# murdock_mcu.net
KiCad netlist of a schematic drawn in EAGLE
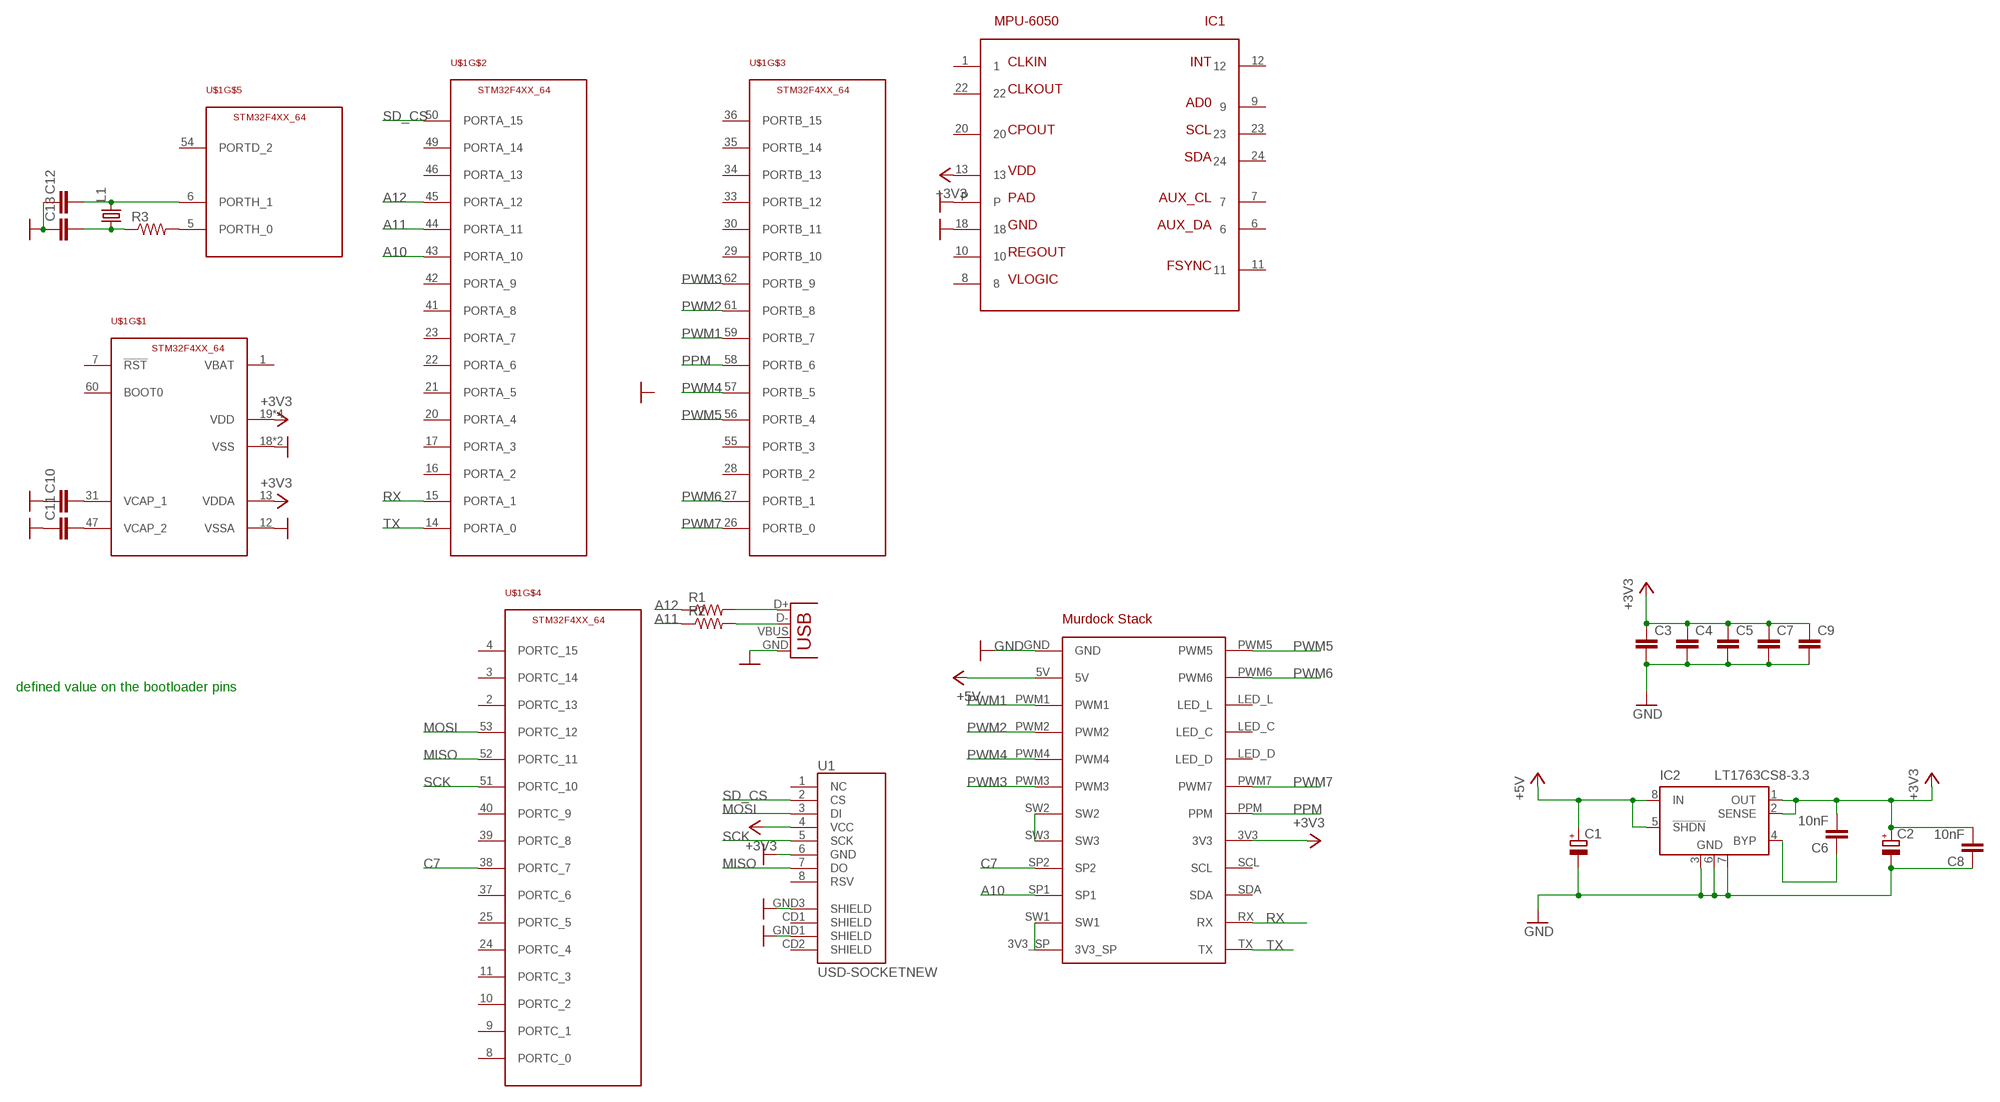
[diagram p0: schematic, sheet 1]

(export (version "E")
  (design (tool "Eeschema 10.0.6"))
  (components
    (comp (ref "C1")
      (value "CPOL-EUSMCD")
      (footprint "eagle-import:SMC_D")
      (libsource (lib "eagle-import") (part "CPOL-EUSMCD"))
    )
    (comp (ref "C2")
      (value "CPOL-EUSMCD")
      (footprint "eagle-import:SMC_D")
      (libsource (lib "eagle-import") (part "CPOL-EUSMCD"))
    )
    (comp (ref "C3")
      (value "CAP0402-CAP")
      (footprint "eagle-import:0402-CAP")
      (libsource (lib "eagle-import") (part "CAP0402-CAP"))
    )
    (comp (ref "C4")
      (value "CAP0402-CAP")
      (footprint "eagle-import:0402-CAP")
      (libsource (lib "eagle-import") (part "CAP0402-CAP"))
    )
    (comp (ref "C5")
      (value "CAP0402-CAP")
      (footprint "eagle-import:0402-CAP")
      (libsource (lib "eagle-import") (part "CAP0402-CAP"))
    )
    (comp (ref "C6")
      (value "10nF")
      (footprint "eagle-import:C0402")
      (libsource (lib "eagle-import") (part "C-EUC0402"))
    )
    (comp (ref "C7")
      (value "CAP0402-CAP")
      (footprint "eagle-import:0402-CAP")
      (libsource (lib "eagle-import") (part "CAP0402-CAP"))
    )
    (comp (ref "C8")
      (value "10nF")
      (footprint "eagle-import:C0402")
      (libsource (lib "eagle-import") (part "C-EUC0402"))
    )
    (comp (ref "C9")
      (value "CAP0402-CAP")
      (footprint "eagle-import:0402-CAP")
      (libsource (lib "eagle-import") (part "CAP0402-CAP"))
    )
    (comp (ref "C10")
      (value "CAP0805")
      (footprint "eagle-import:0805")
      (libsource (lib "eagle-import") (part "CAP0805"))
    )
    (comp (ref "C11")
      (value "CAP0805")
      (footprint "eagle-import:0805")
      (libsource (lib "eagle-import") (part "CAP0805"))
    )
    (comp (ref "C12")
      (value "CAP0402-CAP")
      (footprint "eagle-import:0402-CAP")
      (libsource (lib "eagle-import") (part "CAP0402-CAP"))
    )
    (comp (ref "C13")
      (value "CAP0402-CAP")
      (footprint "eagle-import:0402-CAP")
      (libsource (lib "eagle-import") (part "CAP0402-CAP"))
    )
    (comp (ref "IC1")
      (value "MPU-6050")
      (footprint "eagle-import:QFN24")
      (libsource (lib "eagle-import") (part "MPU-6050"))
    )
    (comp (ref "IC2")
      (value "LT1763CS8-3.3")
      (footprint "eagle-import:SOIC8")
      (libsource (lib "eagle-import") (part "LT1763CS8-3.3"))
    )
    (comp (ref "L1")
      (value "X22-OSCILLATOR")
      (footprint "eagle-import:X22")
      (libsource (lib "eagle-import") (part "X22-OSCILLATOR"))
    )
    (comp (ref "R1")
      (value "RESISTOR0402-RES")
      (footprint "eagle-import:0402-RES")
      (libsource (lib "eagle-import") (part "RESISTOR0402-RES"))
    )
    (comp (ref "R2")
      (value "RESISTOR0402-RES")
      (footprint "eagle-import:0402-RES")
      (libsource (lib "eagle-import") (part "RESISTOR0402-RES"))
    )
    (comp (ref "R3")
      (value "RESISTOR0402-RES")
      (footprint "eagle-import:0402-RES")
      (libsource (lib "eagle-import") (part "RESISTOR0402-RES"))
    )
    (comp (ref "U$1")
      (value "STM32F4XX_64")
      (footprint "eagle-import:TQFP64")
      (libsource (lib "eagle-import") (part "STM32F4XX_64"))
    )
    (comp (ref "U1")
      (value "USD-SOCKETNEW")
      (footprint "eagle-import:MICRO-SD-SOCKET-PP")
      (libsource (lib "eagle-import") (part "USD-SOCKETNEW"))
    )
    (comp (ref "X1")
      (value "USBSMD")
      (footprint "eagle-import:USB-MINIB")
      (libsource (lib "eagle-import") (part "USBSMD"))
    )
    (comp (ref "X2")
      (value "MURDOCK_STACK")
      (footprint "eagle-import:MURDOCK_STACK")
      (libsource (lib "eagle-import") (part "MURDOCK_STACK"))
    )
  )
  (nets
    (net (code "1") (name "+3V3") (class "Default")
      (node (ref "C2") (pin "+") (pinfunction "+_+") (pintype "passive"))
      (node (ref "C3") (pin "1") (pinfunction "1_1") (pintype "passive"))
      (node (ref "C4") (pin "1") (pinfunction "1_1") (pintype "passive"))
      (node (ref "C5") (pin "1") (pinfunction "1_1") (pintype "passive"))
      (node (ref "C6") (pin "2") (pinfunction "2_2") (pintype "passive"))
      (node (ref "C7") (pin "1") (pinfunction "1_1") (pintype "passive"))
      (node (ref "C8") (pin "2") (pinfunction "2_2") (pintype "passive"))
      (node (ref "C9") (pin "1") (pinfunction "1_1") (pintype "passive"))
      (node (ref "IC1") (pin "13") (pinfunction "13_13") (pintype "bidirectional"))
      (node (ref "IC2") (pin "1") (pinfunction "OUT_1") (pintype "passive"))
      (node (ref "IC2") (pin "2") (pinfunction "SENSE_2") (pintype "input"))
      (node (ref "U$1") (pin "13") (pinfunction "VDDA_13") (pintype "bidirectional"))
      (node (ref "U$1") (pin "19") (pinfunction "VDD_19") (pintype "bidirectional"))
      (node (ref "U$1") (pin "32") (pinfunction "VDD_32") (pintype "bidirectional"))
      (node (ref "U$1") (pin "48") (pinfunction "VDD_48") (pintype "bidirectional"))
      (node (ref "U$1") (pin "64") (pinfunction "VDD_64") (pintype "bidirectional"))
      (node (ref "U1") (pin "4") (pinfunction "VCC_4") (pintype "bidirectional"))
      (node (ref "X2") (pin "3V3") (pinfunction "3V3_3V3") (pintype "bidirectional"))
    )
    (net (code "2") (name "+5V") (class "Default")
      (node (ref "C1") (pin "+") (pinfunction "+_+") (pintype "passive"))
      (node (ref "IC2") (pin "5") (pinfunction "~{SHDN}_5") (pintype "input"))
      (node (ref "IC2") (pin "8") (pinfunction "IN_8") (pintype "input"))
      (node (ref "X2") (pin "5V") (pinfunction "5V_5V") (pintype "bidirectional"))
    )
    (net (code "3") (name "A10") (class "Default")
      (node (ref "U$1") (pin "43") (pinfunction "PORTA_10_43") (pintype "bidirectional"))
      (node (ref "X2") (pin "SP1") (pinfunction "SP1_SP1") (pintype "bidirectional"))
    )
    (net (code "4") (name "A11") (class "Default")
      (node (ref "R2") (pin "1") (pinfunction "1_1") (pintype "passive"))
      (node (ref "U$1") (pin "44") (pinfunction "PORTA_11_44") (pintype "bidirectional"))
    )
    (net (code "5") (name "A12") (class "Default")
      (node (ref "R1") (pin "1") (pinfunction "1_1") (pintype "passive"))
      (node (ref "U$1") (pin "45") (pinfunction "PORTA_12_45") (pintype "bidirectional"))
    )
    (net (code "6") (name "C7") (class "Default")
      (node (ref "U$1") (pin "38") (pinfunction "PORTC_7_38") (pintype "bidirectional"))
      (node (ref "X2") (pin "SP2") (pinfunction "SP2_SP2") (pintype "bidirectional"))
    )
    (net (code "7") (name "GND") (class "Default")
      (node (ref "C1") (pin "-") (pinfunction "-_-") (pintype "passive"))
      (node (ref "C10") (pin "1") (pinfunction "1_1") (pintype "passive"))
      (node (ref "C11") (pin "1") (pinfunction "1_1") (pintype "passive"))
      (node (ref "C12") (pin "1") (pinfunction "1_1") (pintype "passive"))
      (node (ref "C13") (pin "1") (pinfunction "1_1") (pintype "passive"))
      (node (ref "C2") (pin "-") (pinfunction "-_-") (pintype "passive"))
      (node (ref "C3") (pin "2") (pinfunction "2_2") (pintype "passive"))
      (node (ref "C4") (pin "2") (pinfunction "2_2") (pintype "passive"))
      (node (ref "C5") (pin "2") (pinfunction "2_2") (pintype "passive"))
      (node (ref "C7") (pin "2") (pinfunction "2_2") (pintype "passive"))
      (node (ref "C8") (pin "1") (pinfunction "1_1") (pintype "passive"))
      (node (ref "C9") (pin "2") (pinfunction "2_2") (pintype "passive"))
      (node (ref "IC1") (pin "18") (pinfunction "18_18") (pintype "bidirectional"))
      (node (ref "IC1") (pin "P") (pinfunction "P_P") (pintype "bidirectional"))
      (node (ref "IC2") (pin "3") (pinfunction "GND_3") (pintype "power_in"))
      (node (ref "IC2") (pin "6") (pinfunction "GND_6") (pintype "power_in"))
      (node (ref "IC2") (pin "7") (pinfunction "GND_7") (pintype "power_in"))
      (node (ref "U$1") (pin "12") (pinfunction "VSSA_12") (pintype "bidirectional"))
      (node (ref "U$1") (pin "18") (pinfunction "VSS_18") (pintype "bidirectional"))
      (node (ref "U$1") (pin "63") (pinfunction "VSS_63") (pintype "bidirectional"))
      (node (ref "U1") (pin "6") (pinfunction "GND_6") (pintype "bidirectional"))
      (node (ref "U1") (pin "GND1") (pinfunction "SHIELD_GND1") (pintype "bidirectional"))
      (node (ref "U1") (pin "GND3") (pinfunction "SHIELD_GND3") (pintype "bidirectional"))
      (node (ref "X1") (pin "GND") (pinfunction "GND_GND") (pintype "bidirectional"))
      (node (ref "X2") (pin "GND") (pinfunction "GND_GND") (pintype "bidirectional"))
    )
    (net (code "8") (name "MISO") (class "Default")
      (node (ref "U$1") (pin "52") (pinfunction "PORTC_11_52") (pintype "bidirectional"))
      (node (ref "U1") (pin "7") (pinfunction "DO_7") (pintype "bidirectional"))
    )
    (net (code "9") (name "MOSI") (class "Default")
      (node (ref "U$1") (pin "53") (pinfunction "PORTC_12_53") (pintype "bidirectional"))
      (node (ref "U1") (pin "3") (pinfunction "DI_3") (pintype "bidirectional"))
    )
    (net (code "10") (name "Net-(C13-Pad2)") (class "Default")
      (node (ref "C13") (pin "2") (pinfunction "2_2") (pintype "passive"))
      (node (ref "L1") (pin "1") (pinfunction "1_1") (pintype "passive"))
      (node (ref "R3") (pin "1") (pinfunction "1_1") (pintype "passive"))
    )
    (net (code "11") (name "Net-(IC2-BYP)") (class "Default")
      (node (ref "C6") (pin "1") (pinfunction "1_1") (pintype "passive"))
      (node (ref "IC2") (pin "4") (pinfunction "BYP_4") (pintype "input"))
    )
    (net (code "12") (name "Net-(L1-2)") (class "Default")
      (node (ref "C12") (pin "2") (pinfunction "2_2") (pintype "passive"))
      (node (ref "L1") (pin "3") (pinfunction "2_3") (pintype "passive"))
      (node (ref "U$1") (pin "6") (pinfunction "PORTH_1_6") (pintype "bidirectional"))
    )
    (net (code "13") (name "Net-(R1-Pad2)") (class "Default")
      (node (ref "R1") (pin "2") (pinfunction "2_2") (pintype "passive"))
      (node (ref "X1") (pin "D+") (pinfunction "D+_D+") (pintype "bidirectional"))
    )
    (net (code "14") (name "Net-(R2-Pad2)") (class "Default")
      (node (ref "R2") (pin "2") (pinfunction "2_2") (pintype "passive"))
      (node (ref "X1") (pin "D-") (pinfunction "D-_D-") (pintype "bidirectional"))
    )
    (net (code "15") (name "Net-(U$1A-VCAP_1)") (class "Default")
      (node (ref "C10") (pin "2") (pinfunction "2_2") (pintype "passive"))
      (node (ref "U$1") (pin "31") (pinfunction "VCAP_1_31") (pintype "bidirectional"))
    )
    (net (code "16") (name "Net-(U$1A-VCAP_2)") (class "Default")
      (node (ref "C11") (pin "2") (pinfunction "2_2") (pintype "passive"))
      (node (ref "U$1") (pin "47") (pinfunction "VCAP_2_47") (pintype "bidirectional"))
    )
    (net (code "17") (name "Net-(U$1E-PORTH_0)") (class "Default")
      (node (ref "R3") (pin "2") (pinfunction "2_2") (pintype "passive"))
      (node (ref "U$1") (pin "5") (pinfunction "PORTH_0_5") (pintype "bidirectional"))
    )
    (net (code "18") (name "Net-(X2-Pad3V3_SP)") (class "Default")
      (node (ref "X2") (pin "3V3_SP") (pinfunction "3V3_SP_3V3_SP") (pintype "bidirectional"))
      (node (ref "X2") (pin "SW1") (pinfunction "SW1_SW1") (pintype "bidirectional"))
    )
    (net (code "19") (name "Net-(X2-PadSW2)") (class "Default")
      (node (ref "X2") (pin "SW2") (pinfunction "SW2_SW2") (pintype "bidirectional"))
      (node (ref "X2") (pin "SW3") (pinfunction "SW3_SW3") (pintype "bidirectional"))
    )
    (net (code "20") (name "PPM") (class "Default")
      (node (ref "U$1") (pin "58") (pinfunction "PORTB_6_58") (pintype "bidirectional"))
      (node (ref "X2") (pin "PPM") (pinfunction "PPM_PPM") (pintype "bidirectional"))
    )
    (net (code "21") (name "PWM1") (class "Default")
      (node (ref "U$1") (pin "59") (pinfunction "PORTB_7_59") (pintype "bidirectional"))
      (node (ref "X2") (pin "PWM1") (pinfunction "PWM1_PWM1") (pintype "bidirectional"))
    )
    (net (code "22") (name "PWM2") (class "Default")
      (node (ref "U$1") (pin "61") (pinfunction "PORTB_8_61") (pintype "bidirectional"))
      (node (ref "X2") (pin "PWM2") (pinfunction "PWM2_PWM2") (pintype "bidirectional"))
    )
    (net (code "23") (name "PWM3") (class "Default")
      (node (ref "U$1") (pin "62") (pinfunction "PORTB_9_62") (pintype "bidirectional"))
      (node (ref "X2") (pin "PWM3") (pinfunction "PWM3_PWM3") (pintype "bidirectional"))
    )
    (net (code "24") (name "PWM4") (class "Default")
      (node (ref "U$1") (pin "57") (pinfunction "PORTB_5_57") (pintype "bidirectional"))
      (node (ref "X2") (pin "PWM4") (pinfunction "PWM4_PWM4") (pintype "bidirectional"))
    )
    (net (code "25") (name "PWM5") (class "Default")
      (node (ref "U$1") (pin "56") (pinfunction "PORTB_4_56") (pintype "bidirectional"))
      (node (ref "X2") (pin "PWM5") (pinfunction "PWM5_PWM5") (pintype "bidirectional"))
    )
    (net (code "26") (name "PWM6") (class "Default")
      (node (ref "U$1") (pin "27") (pinfunction "PORTB_1_27") (pintype "bidirectional"))
      (node (ref "X2") (pin "PWM6") (pinfunction "PWM6_PWM6") (pintype "bidirectional"))
    )
    (net (code "27") (name "PWM7") (class "Default")
      (node (ref "U$1") (pin "26") (pinfunction "PORTB_0_26") (pintype "bidirectional"))
      (node (ref "X2") (pin "PWM7") (pinfunction "PWM7_PWM7") (pintype "bidirectional"))
    )
    (net (code "28") (name "RX") (class "Default")
      (node (ref "U$1") (pin "15") (pinfunction "PORTA_1_15") (pintype "bidirectional"))
      (node (ref "X2") (pin "RX") (pinfunction "RX_RX") (pintype "bidirectional"))
    )
    (net (code "29") (name "SCK") (class "Default")
      (node (ref "U$1") (pin "51") (pinfunction "PORTC_10_51") (pintype "bidirectional"))
      (node (ref "U1") (pin "5") (pinfunction "SCK_5") (pintype "bidirectional"))
    )
    (net (code "30") (name "SD_CS") (class "Default")
      (node (ref "U$1") (pin "50") (pinfunction "PORTA_15_50") (pintype "bidirectional"))
      (node (ref "U1") (pin "2") (pinfunction "CS_2") (pintype "bidirectional"))
    )
    (net (code "31") (name "TX") (class "Default")
      (node (ref "U$1") (pin "14") (pinfunction "PORTA_0_14") (pintype "bidirectional"))
      (node (ref "X2") (pin "TX") (pinfunction "TX_TX") (pintype "bidirectional"))
    )
    (net (code "32") (name "unconnected-(IC1-Pad1)") (class "Default")
      (node (ref "IC1") (pin "1") (pinfunction "1_1") (pintype "bidirectional"))
    )
    (net (code "33") (name "unconnected-(IC1-Pad6)") (class "Default")
      (node (ref "IC1") (pin "6") (pinfunction "6_6") (pintype "bidirectional"))
    )
    (net (code "34") (name "unconnected-(IC1-Pad7)") (class "Default")
      (node (ref "IC1") (pin "7") (pinfunction "7_7") (pintype "bidirectional"))
    )
    (net (code "35") (name "unconnected-(IC1-Pad8)") (class "Default")
      (node (ref "IC1") (pin "8") (pinfunction "8_8") (pintype "bidirectional"))
    )
    (net (code "36") (name "unconnected-(IC1-Pad9)") (class "Default")
      (node (ref "IC1") (pin "9") (pinfunction "9_9") (pintype "bidirectional"))
    )
    (net (code "37") (name "unconnected-(IC1-Pad10)") (class "Default")
      (node (ref "IC1") (pin "10") (pinfunction "10_10") (pintype "bidirectional"))
    )
    (net (code "38") (name "unconnected-(IC1-Pad11)") (class "Default")
      (node (ref "IC1") (pin "11") (pinfunction "11_11") (pintype "bidirectional"))
    )
    (net (code "39") (name "unconnected-(IC1-Pad12)") (class "Default")
      (node (ref "IC1") (pin "12") (pinfunction "12_12") (pintype "bidirectional"))
    )
    (net (code "40") (name "unconnected-(IC1-Pad20)") (class "Default")
      (node (ref "IC1") (pin "20") (pinfunction "20_20") (pintype "bidirectional"))
    )
    (net (code "41") (name "unconnected-(IC1-Pad22)") (class "Default")
      (node (ref "IC1") (pin "22") (pinfunction "22_22") (pintype "bidirectional"))
    )
    (net (code "42") (name "unconnected-(IC1-Pad23)") (class "Default")
      (node (ref "IC1") (pin "23") (pinfunction "23_23") (pintype "bidirectional"))
    )
    (net (code "43") (name "unconnected-(IC1-Pad24)") (class "Default")
      (node (ref "IC1") (pin "24") (pinfunction "24_24") (pintype "bidirectional"))
    )
    (net (code "44") (name "unconnected-(U$1A-BOOT0-Pad60)") (class "Default")
      (node (ref "U$1") (pin "60") (pinfunction "BOOT0_60") (pintype "bidirectional"))
    )
    (net (code "45") (name "unconnected-(U$1A-VBAT-Pad1)") (class "Default")
      (node (ref "U$1") (pin "1") (pinfunction "VBAT_1") (pintype "bidirectional"))
    )
    (net (code "46") (name "unconnected-(U$1A-~{RST}-Pad7)") (class "Default")
      (node (ref "U$1") (pin "7") (pinfunction "~{RST}_7") (pintype "bidirectional"))
    )
    (net (code "47") (name "unconnected-(U$1B-PORTA_2-Pad16)") (class "Default")
      (node (ref "U$1") (pin "16") (pinfunction "PORTA_2_16") (pintype "bidirectional"))
    )
    (net (code "48") (name "unconnected-(U$1B-PORTA_3-Pad17)") (class "Default")
      (node (ref "U$1") (pin "17") (pinfunction "PORTA_3_17") (pintype "bidirectional"))
    )
    (net (code "49") (name "unconnected-(U$1B-PORTA_4-Pad20)") (class "Default")
      (node (ref "U$1") (pin "20") (pinfunction "PORTA_4_20") (pintype "bidirectional"))
    )
    (net (code "50") (name "unconnected-(U$1B-PORTA_5-Pad21)") (class "Default")
      (node (ref "U$1") (pin "21") (pinfunction "PORTA_5_21") (pintype "bidirectional"))
    )
    (net (code "51") (name "unconnected-(U$1B-PORTA_6-Pad22)") (class "Default")
      (node (ref "U$1") (pin "22") (pinfunction "PORTA_6_22") (pintype "bidirectional"))
    )
    (net (code "52") (name "unconnected-(U$1B-PORTA_7-Pad23)") (class "Default")
      (node (ref "U$1") (pin "23") (pinfunction "PORTA_7_23") (pintype "bidirectional"))
    )
    (net (code "53") (name "unconnected-(U$1B-PORTA_8-Pad41)") (class "Default")
      (node (ref "U$1") (pin "41") (pinfunction "PORTA_8_41") (pintype "bidirectional"))
    )
    (net (code "54") (name "unconnected-(U$1B-PORTA_9-Pad42)") (class "Default")
      (node (ref "U$1") (pin "42") (pinfunction "PORTA_9_42") (pintype "bidirectional"))
    )
    (net (code "55") (name "unconnected-(U$1B-PORTA_13-Pad46)") (class "Default")
      (node (ref "U$1") (pin "46") (pinfunction "PORTA_13_46") (pintype "bidirectional"))
    )
    (net (code "56") (name "unconnected-(U$1B-PORTA_14-Pad49)") (class "Default")
      (node (ref "U$1") (pin "49") (pinfunction "PORTA_14_49") (pintype "bidirectional"))
    )
    (net (code "57") (name "unconnected-(U$1C-PORTB_2-Pad28)") (class "Default")
      (node (ref "U$1") (pin "28") (pinfunction "PORTB_2_28") (pintype "bidirectional"))
    )
    (net (code "58") (name "unconnected-(U$1C-PORTB_3-Pad55)") (class "Default")
      (node (ref "U$1") (pin "55") (pinfunction "PORTB_3_55") (pintype "bidirectional"))
    )
    (net (code "59") (name "unconnected-(U$1C-PORTB_10-Pad29)") (class "Default")
      (node (ref "U$1") (pin "29") (pinfunction "PORTB_10_29") (pintype "bidirectional"))
    )
    (net (code "60") (name "unconnected-(U$1C-PORTB_11-Pad30)") (class "Default")
      (node (ref "U$1") (pin "30") (pinfunction "PORTB_11_30") (pintype "bidirectional"))
    )
    (net (code "61") (name "unconnected-(U$1C-PORTB_12-Pad33)") (class "Default")
      (node (ref "U$1") (pin "33") (pinfunction "PORTB_12_33") (pintype "bidirectional"))
    )
    (net (code "62") (name "unconnected-(U$1C-PORTB_13-Pad34)") (class "Default")
      (node (ref "U$1") (pin "34") (pinfunction "PORTB_13_34") (pintype "bidirectional"))
    )
    (net (code "63") (name "unconnected-(U$1C-PORTB_14-Pad35)") (class "Default")
      (node (ref "U$1") (pin "35") (pinfunction "PORTB_14_35") (pintype "bidirectional"))
    )
    (net (code "64") (name "unconnected-(U$1C-PORTB_15-Pad36)") (class "Default")
      (node (ref "U$1") (pin "36") (pinfunction "PORTB_15_36") (pintype "bidirectional"))
    )
    (net (code "65") (name "unconnected-(U$1D-PORTC_0-Pad8)") (class "Default")
      (node (ref "U$1") (pin "8") (pinfunction "PORTC_0_8") (pintype "bidirectional"))
    )
    (net (code "66") (name "unconnected-(U$1D-PORTC_1-Pad9)") (class "Default")
      (node (ref "U$1") (pin "9") (pinfunction "PORTC_1_9") (pintype "bidirectional"))
    )
    (net (code "67") (name "unconnected-(U$1D-PORTC_2-Pad10)") (class "Default")
      (node (ref "U$1") (pin "10") (pinfunction "PORTC_2_10") (pintype "bidirectional"))
    )
    (net (code "68") (name "unconnected-(U$1D-PORTC_3-Pad11)") (class "Default")
      (node (ref "U$1") (pin "11") (pinfunction "PORTC_3_11") (pintype "bidirectional"))
    )
    (net (code "69") (name "unconnected-(U$1D-PORTC_4-Pad24)") (class "Default")
      (node (ref "U$1") (pin "24") (pinfunction "PORTC_4_24") (pintype "bidirectional"))
    )
    (net (code "70") (name "unconnected-(U$1D-PORTC_5-Pad25)") (class "Default")
      (node (ref "U$1") (pin "25") (pinfunction "PORTC_5_25") (pintype "bidirectional"))
    )
    (net (code "71") (name "unconnected-(U$1D-PORTC_6-Pad37)") (class "Default")
      (node (ref "U$1") (pin "37") (pinfunction "PORTC_6_37") (pintype "bidirectional"))
    )
    (net (code "72") (name "unconnected-(U$1D-PORTC_8-Pad39)") (class "Default")
      (node (ref "U$1") (pin "39") (pinfunction "PORTC_8_39") (pintype "bidirectional"))
    )
    (net (code "73") (name "unconnected-(U$1D-PORTC_9-Pad40)") (class "Default")
      (node (ref "U$1") (pin "40") (pinfunction "PORTC_9_40") (pintype "bidirectional"))
    )
    (net (code "74") (name "unconnected-(U$1D-PORTC_13-Pad2)") (class "Default")
      (node (ref "U$1") (pin "2") (pinfunction "PORTC_13_2") (pintype "bidirectional"))
    )
    (net (code "75") (name "unconnected-(U$1D-PORTC_14-Pad3)") (class "Default")
      (node (ref "U$1") (pin "3") (pinfunction "PORTC_14_3") (pintype "bidirectional"))
    )
    (net (code "76") (name "unconnected-(U$1D-PORTC_15-Pad4)") (class "Default")
      (node (ref "U$1") (pin "4") (pinfunction "PORTC_15_4") (pintype "bidirectional"))
    )
    (net (code "77") (name "unconnected-(U$1E-PORTD_2-Pad54)") (class "Default")
      (node (ref "U$1") (pin "54") (pinfunction "PORTD_2_54") (pintype "bidirectional"))
    )
    (net (code "78") (name "unconnected-(U1-NC-Pad1)") (class "Default")
      (node (ref "U1") (pin "1") (pinfunction "NC_1") (pintype "bidirectional"))
    )
    (net (code "79") (name "unconnected-(U1-RSV-Pad8)") (class "Default")
      (node (ref "U1") (pin "8") (pinfunction "RSV_8") (pintype "bidirectional"))
    )
    (net (code "80") (name "unconnected-(U1-SHIELD-PadCD1)") (class "Default")
      (node (ref "U1") (pin "CD1") (pinfunction "SHIELD_CD1") (pintype "bidirectional"))
    )
    (net (code "81") (name "unconnected-(U1-SHIELD-PadCD2)") (class "Default")
      (node (ref "U1") (pin "CD2") (pinfunction "SHIELD_CD2") (pintype "bidirectional"))
    )
    (net (code "82") (name "unconnected-(X1-PadVBUS)") (class "Default")
      (node (ref "X1") (pin "VBUS") (pinfunction "VBUS_VBUS") (pintype "bidirectional"))
    )
    (net (code "83") (name "unconnected-(X2-PadLED_C)") (class "Default")
      (node (ref "X2") (pin "LED_C") (pinfunction "LED_C_LED_C") (pintype "bidirectional"))
    )
    (net (code "84") (name "unconnected-(X2-PadLED_D)") (class "Default")
      (node (ref "X2") (pin "LED_D") (pinfunction "LED_D_LED_D") (pintype "bidirectional"))
    )
    (net (code "85") (name "unconnected-(X2-PadLED_L)") (class "Default")
      (node (ref "X2") (pin "LED_L") (pinfunction "LED_L_LED_L") (pintype "bidirectional"))
    )
    (net (code "86") (name "unconnected-(X2-PadSCL)") (class "Default")
      (node (ref "X2") (pin "SCL") (pinfunction "SCL_SCL") (pintype "bidirectional"))
    )
    (net (code "87") (name "unconnected-(X2-PadSDA)") (class "Default")
      (node (ref "X2") (pin "SDA") (pinfunction "SDA_SDA") (pintype "bidirectional"))
    )
  )
)
